# -YL-800TS.net
KiCad netlist of a schematic drawn in Altium Designer
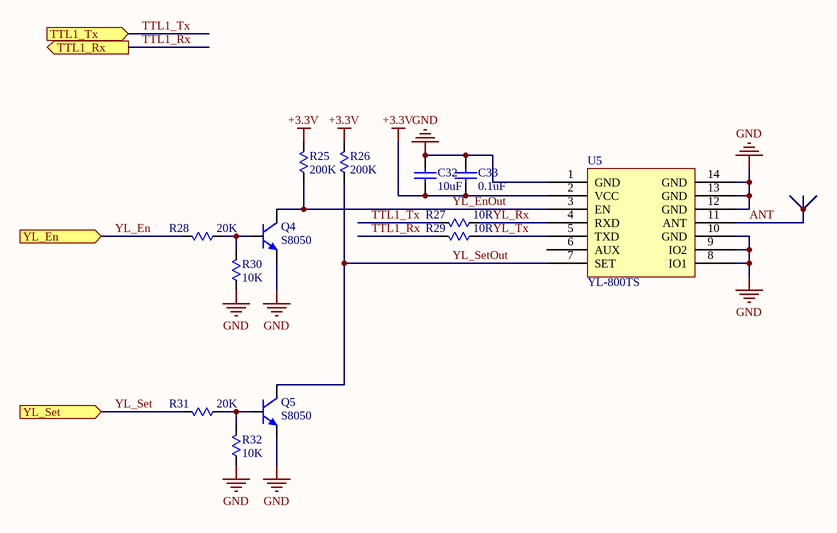
[diagram p0: 电子脚铐便携式主控板-YL-800TS.SchDoc]

(export (version "E")
  (design (tool "Eeschema 10.0.6"))
  (components
    (comp (ref "C32")
      (value "10uF")
      (footprint "C0603")
      (description "CAP")
      (fields (field (name "PUBLISHER") "Altium Limited"))
      (libsource (lib "Passive Components Class") (part "CAP"))
    )
    (comp (ref "C33")
      (value "0.1uF")
      (footprint "C0603")
      (description "CAP")
      (fields (field (name "PUBLISHER") "Altium Limited"))
      (libsource (lib "Passive Components Class") (part "CAP"))
    )
    (comp (ref "Q4")
      (value "S8050")
      (footprint "SOT-23")
      (description "NPN triode, 0.5A Max")
      (libsource (lib "RLCYDF") (part "S8050"))
    )
    (comp (ref "Q5")
      (value "S8050")
      (footprint "SOT-23")
      (description "NPN triode, 0.5A Max")
      (libsource (lib "RLCYDF") (part "S8050"))
    )
    (comp (ref "R25")
      (value "200K")
      (footprint "R0603")
      (description "Resistor")
      (fields (field (name "PUBLISHER") "Altium Limited"))
      (libsource (lib "Passive Components Class") (part "RES"))
    )
    (comp (ref "R26")
      (value "200K")
      (footprint "R0603")
      (description "Resistor")
      (fields (field (name "PUBLISHER") "Altium Limited"))
      (libsource (lib "Passive Components Class") (part "RES"))
    )
    (comp (ref "R27")
      (value "10R")
      (footprint "R0603")
      (description "Resistor")
      (fields (field (name "Comment") "200K") (field (name "PUBLISHER") "Altium Limited"))
      (libsource (lib "Passive Components Class") (part "RES"))
    )
    (comp (ref "R28")
      (value "20K")
      (footprint "R0603")
      (description "Resistor")
      (fields (field (name "Comment") "200K") (field (name "PUBLISHER") "Altium Limited"))
      (libsource (lib "Passive Components Class") (part "RES"))
    )
    (comp (ref "R29")
      (value "10R")
      (footprint "R0603")
      (description "Resistor")
      (fields (field (name "Comment") "200K") (field (name "PUBLISHER") "Altium Limited"))
      (libsource (lib "Passive Components Class") (part "RES"))
    )
    (comp (ref "R30")
      (value "10K")
      (footprint "R0603")
      (description "Resistor")
      (fields (field (name "PUBLISHER") "Altium Limited"))
      (libsource (lib "Passive Components Class") (part "RES"))
    )
    (comp (ref "R31")
      (value "20K")
      (footprint "R0603")
      (description "Resistor")
      (fields (field (name "Comment") "200K") (field (name "PUBLISHER") "Altium Limited"))
      (libsource (lib "Passive Components Class") (part "RES"))
    )
    (comp (ref "R32")
      (value "10K")
      (footprint "R0603")
      (description "Resistor")
      (fields (field (name "PUBLISHER") "Altium Limited"))
      (libsource (lib "Passive Components Class") (part "RES"))
    )
    (comp (ref "U5") (value "YL-800TS") (footprint "YL-800TS") (libsource (lib "Module") (part "YL-800TS")))
  )
  (nets
    (net (code "1") (name "+3.3V") (class "Default")
      (node (ref "C32") (pin "1") (pinfunction "1_1") (pintype "passive"))
      (node (ref "C33") (pin "1") (pinfunction "1_1") (pintype "passive"))
      (node (ref "R25") (pin "2") (pinfunction "2_2") (pintype "passive"))
      (node (ref "R26") (pin "2") (pinfunction "2_2") (pintype "passive"))
      (node (ref "U5") (pin "2") (pinfunction "VCC_2") (pintype "passive"))
    )
    (net (code "2") (name "/ANT") (class "Default")
      (node (ref "U5") (pin "11") (pinfunction "ANT_11") (pintype "passive"))
    )
    (net (code "3") (name "/TTL1_Rx") (class "Default")
      (node (ref "R29") (pin "2") (pinfunction "2_2") (pintype "passive"))
    )
    (net (code "4") (name "/TTL1_Tx") (class "Default")
      (node (ref "R27") (pin "2") (pinfunction "2_2") (pintype "passive"))
    )
    (net (code "5") (name "/YL_En") (class "Default")
      (node (ref "R28") (pin "2") (pinfunction "2_2") (pintype "passive"))
    )
    (net (code "6") (name "/YL_EnOut") (class "Default")
      (node (ref "Q4") (pin "3") (pinfunction "c_3") (pintype "passive"))
      (node (ref "R25") (pin "1") (pinfunction "1_1") (pintype "passive"))
      (node (ref "U5") (pin "3") (pinfunction "EN_3") (pintype "passive"))
    )
    (net (code "7") (name "/YL_Rx") (class "Default")
      (node (ref "R27") (pin "1") (pinfunction "1_1") (pintype "passive"))
      (node (ref "U5") (pin "4") (pinfunction "RXD_4") (pintype "passive"))
    )
    (net (code "8") (name "/YL_Set") (class "Default")
      (node (ref "R31") (pin "2") (pinfunction "2_2") (pintype "passive"))
    )
    (net (code "9") (name "/YL_SetOut") (class "Default")
      (node (ref "Q5") (pin "3") (pinfunction "c_3") (pintype "passive"))
      (node (ref "R26") (pin "1") (pinfunction "1_1") (pintype "passive"))
      (node (ref "U5") (pin "7") (pinfunction "SET_7") (pintype "passive"))
    )
    (net (code "10") (name "/YL_Tx") (class "Default")
      (node (ref "R29") (pin "1") (pinfunction "1_1") (pintype "passive"))
      (node (ref "U5") (pin "5") (pinfunction "TXD_5") (pintype "passive"))
    )
    (net (code "11") (name "GND") (class "Default")
      (node (ref "C32") (pin "2") (pinfunction "2_2") (pintype "passive"))
      (node (ref "C33") (pin "2") (pinfunction "2_2") (pintype "passive"))
      (node (ref "Q4") (pin "2") (pinfunction "e_2") (pintype "passive"))
      (node (ref "Q5") (pin "2") (pinfunction "e_2") (pintype "passive"))
      (node (ref "R30") (pin "1") (pinfunction "1_1") (pintype "passive"))
      (node (ref "R32") (pin "1") (pinfunction "1_1") (pintype "passive"))
      (node (ref "U5") (pin "1") (pinfunction "GND_1") (pintype "passive"))
      (node (ref "U5") (pin "10") (pinfunction "GND_10") (pintype "passive"))
      (node (ref "U5") (pin "12") (pinfunction "GND_12") (pintype "passive"))
      (node (ref "U5") (pin "13") (pinfunction "GND_13") (pintype "passive"))
      (node (ref "U5") (pin "14") (pinfunction "GND_14") (pintype "passive"))
      (node (ref "U5") (pin "8") (pinfunction "IO1_8") (pintype "passive"))
      (node (ref "U5") (pin "9") (pinfunction "IO2_9") (pintype "passive"))
    )
    (net (code "12") (name "Net-(Q4-b)") (class "Default")
      (node (ref "Q4") (pin "1") (pinfunction "b_1") (pintype "passive"))
      (node (ref "R28") (pin "1") (pinfunction "1_1") (pintype "passive"))
      (node (ref "R30") (pin "2") (pinfunction "2_2") (pintype "passive"))
    )
    (net (code "13") (name "Net-(Q5-b)") (class "Default")
      (node (ref "Q5") (pin "1") (pinfunction "b_1") (pintype "passive"))
      (node (ref "R31") (pin "1") (pinfunction "1_1") (pintype "passive"))
      (node (ref "R32") (pin "2") (pinfunction "2_2") (pintype "passive"))
    )
    (net (code "14") (name "unconnected-(U5-AUX-Pad6)") (class "Default")
      (node (ref "U5") (pin "6") (pinfunction "AUX_6") (pintype "passive"))
    )
  )
)
